# MCU.net
KiCad netlist of a schematic drawn in Altium Designer
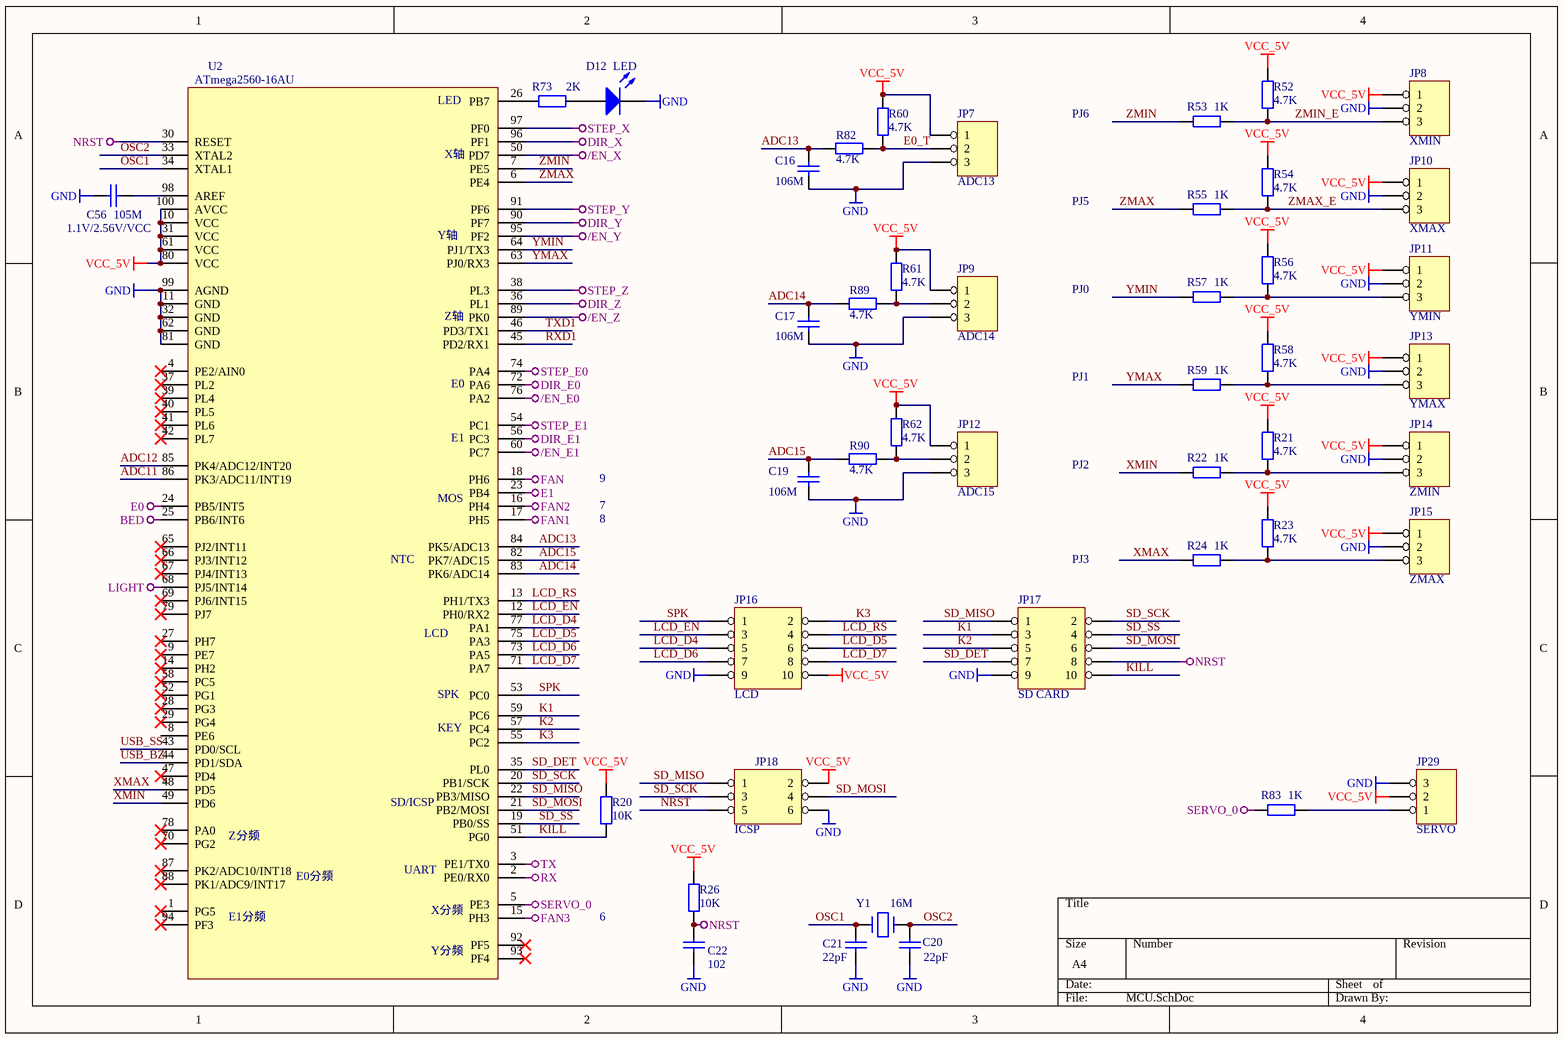
[diagram p0: MCU.SchDoc]

(export (version "E")
  (design (tool "Eeschema 10.0.6"))
  (components
    (comp (ref "C16")
      (value "106M")
      (footprint "0603(C)")
      (description "Capacitor")
      (fields (field (name "PUBLISHER") "Altium Limited"))
      (libsource (lib "Miscellaneous Devices") (part "Cap"))
    )
    (comp (ref "C17")
      (value "106M")
      (footprint "0603(C)")
      (description "Capacitor")
      (fields (field (name "PUBLISHER") "Altium Limited"))
      (libsource (lib "Miscellaneous Devices") (part "Cap"))
    )
    (comp (ref "C19")
      (value "106M")
      (footprint "0603(C)")
      (description "Capacitor")
      (fields (field (name "PUBLISHER") "Altium Limited"))
      (libsource (lib "Miscellaneous Devices") (part "Cap"))
    )
    (comp (ref "C20")
      (value "22pF")
      (footprint "0603(C)")
      (description "Capacitor")
      (fields (field (name "PUBLISHER") "Altium Limited"))
      (libsource (lib "Miscellaneous Devices") (part "Cap"))
    )
    (comp (ref "C21")
      (value "22pF")
      (footprint "0603(C)")
      (description "Capacitor")
      (fields (field (name "PUBLISHER") "Altium Limited"))
      (libsource (lib "Miscellaneous Devices") (part "Cap"))
    )
    (comp (ref "C22")
      (value "102")
      (footprint "0603(C)")
      (description "Capacitor")
      (fields (field (name "PUBLISHER") "Altium Limited"))
      (libsource (lib "Miscellaneous Devices") (part "Cap"))
    )
    (comp (ref "C56")
      (value "105M")
      (footprint "0603(C)")
      (description "Capacitor")
      (fields (field (name "PUBLISHER") "Altium Limited"))
      (libsource (lib "Miscellaneous Devices") (part "Cap"))
    )
    (comp (ref "D12")
      (value "LED")
      (footprint "LED-SMD-0805")
      (description "Typical RED GaAs LED")
      (fields (field (name "PUBLISHER") "Altium Limited"))
      (libsource (lib "Miscellaneous Devices") (part "LED1"))
    )
    (comp (ref "JP7") (value "ADC13") (footprint "XH2.54-3P") (libsource (lib "U_PP SCH") (part "HEADER 3")))
    (comp (ref "JP8") (value "XMIN") (footprint "XH2.54-3P") (libsource (lib "U_PP SCH") (part "HEADER 3")))
    (comp (ref "JP9") (value "ADC14") (footprint "XH2.54-3P") (libsource (lib "U_PP SCH") (part "HEADER 3")))
    (comp (ref "JP10") (value "XMAX") (footprint "XH2.54-3P") (libsource (lib "U_PP SCH") (part "HEADER 3")))
    (comp (ref "JP11") (value "YMIN") (footprint "XH2.54-3P") (libsource (lib "U_PP SCH") (part "HEADER 3")))
    (comp (ref "JP12") (value "ADC15") (footprint "XH2.54-3P") (libsource (lib "U_PP SCH") (part "HEADER 3")))
    (comp (ref "JP13") (value "YMAX") (footprint "XH2.54-3P") (libsource (lib "U_PP SCH") (part "HEADER 3")))
    (comp (ref "JP14") (value "ZMIN") (footprint "XH2.54-3P") (libsource (lib "U_PP SCH") (part "HEADER 3")))
    (comp (ref "JP15") (value "ZMAX") (footprint "XH2.54-3P") (libsource (lib "U_PP SCH") (part "HEADER 3")))
    (comp (ref "JP16")
      (value "LCD")
      (footprint "IDC10-BASE")
      (libsource (lib "U_PP SCH") (part "HEADER 5X2"))
    )
    (comp (ref "JP17")
      (value "SD CARD")
      (footprint "IDC10-BASE")
      (libsource (lib "U_PP SCH") (part "HEADER 5X2"))
    )
    (comp (ref "JP18")
      (value "ICSP")
      (footprint "IDC6X2.54")
      (libsource (lib "U_PP SCH") (part "HEADER 3X2"))
    )
    (comp (ref "JP29") (value "SERVO") (footprint "XH2.54-3P") (libsource (lib "") (part "HEADER 3_1")))
    (comp (ref "R20")
      (value "10K")
      (footprint "0603(R)")
      (description "1K")
      (fields (field (name "PUBLISHER") "Altium Limited"))
      (libsource (lib "") (part "Res2_2"))
    )
    (comp (ref "R21")
      (value "4.7K")
      (footprint "0603(R)")
      (description "1K")
      (fields (field (name "PUBLISHER") "Altium Limited"))
      (libsource (lib "") (part "Res2_1"))
    )
    (comp (ref "R22")
      (value "1K")
      (footprint "0603(R)")
      (fields (field (name "PUBLISHER") "Altium Limited"))
      (libsource (lib "Miscellaneous Devices") (part "Res2"))
    )
    (comp (ref "R23")
      (value "4.7K")
      (footprint "0603(R)")
      (description "1K")
      (fields (field (name "PUBLISHER") "Altium Limited"))
      (libsource (lib "") (part "Res2_1"))
    )
    (comp (ref "R24")
      (value "1K")
      (footprint "0603(R)")
      (fields (field (name "PUBLISHER") "Altium Limited"))
      (libsource (lib "Miscellaneous Devices") (part "Res2"))
    )
    (comp (ref "R26")
      (value "10K")
      (footprint "0603(R)")
      (description "1K")
      (fields (field (name "PUBLISHER") "Altium Limited"))
      (libsource (lib "") (part "Res2_2"))
    )
    (comp (ref "R52")
      (value "4.7K")
      (footprint "0603(R)")
      (description "1K")
      (fields (field (name "PUBLISHER") "Altium Limited"))
      (libsource (lib "") (part "Res2_1"))
    )
    (comp (ref "R53")
      (value "1K")
      (footprint "0603(R)")
      (fields (field (name "PUBLISHER") "Altium Limited"))
      (libsource (lib "Miscellaneous Devices") (part "Res2"))
    )
    (comp (ref "R54")
      (value "4.7K")
      (footprint "0603(R)")
      (description "1K")
      (fields (field (name "PUBLISHER") "Altium Limited"))
      (libsource (lib "") (part "Res2_1"))
    )
    (comp (ref "R55")
      (value "1K")
      (footprint "0603(R)")
      (fields (field (name "PUBLISHER") "Altium Limited"))
      (libsource (lib "Miscellaneous Devices") (part "Res2"))
    )
    (comp (ref "R56")
      (value "4.7K")
      (footprint "0603(R)")
      (description "1K")
      (fields (field (name "PUBLISHER") "Altium Limited"))
      (libsource (lib "") (part "Res2_1"))
    )
    (comp (ref "R57")
      (value "1K")
      (footprint "0603(R)")
      (fields (field (name "PUBLISHER") "Altium Limited"))
      (libsource (lib "Miscellaneous Devices") (part "Res2"))
    )
    (comp (ref "R58")
      (value "4.7K")
      (footprint "0603(R)")
      (description "1K")
      (fields (field (name "PUBLISHER") "Altium Limited"))
      (libsource (lib "") (part "Res2_1"))
    )
    (comp (ref "R59")
      (value "1K")
      (footprint "0603(R)")
      (fields (field (name "PUBLISHER") "Altium Limited"))
      (libsource (lib "Miscellaneous Devices") (part "Res2"))
    )
    (comp (ref "R60")
      (value "4.7K")
      (footprint "0603(R)")
      (description "1K")
      (fields (field (name "PUBLISHER") "Altium Limited"))
      (libsource (lib "") (part "Res2_1"))
    )
    (comp (ref "R61")
      (value "4.7K")
      (footprint "0603(R)")
      (description "1K")
      (fields (field (name "PUBLISHER") "Altium Limited"))
      (libsource (lib "") (part "Res2_1"))
    )
    (comp (ref "R62")
      (value "4.7K")
      (footprint "0603(R)")
      (description "1K")
      (fields (field (name "PUBLISHER") "Altium Limited"))
      (libsource (lib "") (part "Res2_1"))
    )
    (comp (ref "R73")
      (value "2K")
      (footprint "0603(R)")
      (description "Resistor")
      (libsource (lib "*") (part "Res2"))
    )
    (comp (ref "R82")
      (value "4.7K")
      (footprint "0603(R)")
      (description "1K")
      (fields (field (name "PUBLISHER") "Altium Limited"))
      (libsource (lib "") (part "Res2_3"))
    )
    (comp (ref "R83")
      (value "1K")
      (footprint "0603(R)")
      (fields (field (name "PUBLISHER") "Altium Limited"))
      (libsource (lib "Miscellaneous Devices") (part "Res2"))
    )
    (comp (ref "R89")
      (value "4.7K")
      (footprint "0603(R)")
      (description "1K")
      (fields (field (name "PUBLISHER") "Altium Limited"))
      (libsource (lib "") (part "Res2_3"))
    )
    (comp (ref "R90")
      (value "4.7K")
      (footprint "0603(R)")
      (description "1K")
      (fields (field (name "PUBLISHER") "Altium Limited"))
      (libsource (lib "") (part "Res2_3"))
    )
    (comp (ref "U2")
      (value "ATmega2560-16AU")
      (footprint "LQFP100")
      (libsource (lib "U_PP SCH") (part "ATmega2560"))
    )
    (comp (ref "Y1")
      (value "16M")
      (footprint "CRYS-SMD-5032-2P")
      (description "Crystal")
      (libsource (lib "Miscellaneous Devicespp1") (part "CRYSTAL"))
    )
  )
  (nets
    (net (code "1") (name "/ADC11") (class "Default")
      (node (ref "U2") (pin "86") (pinfunction "PK3/ADC11/INT19_86") (pintype "passive"))
    )
    (net (code "2") (name "/ADC12") (class "Default")
      (node (ref "U2") (pin "85") (pinfunction "PK4/ADC12/INT20_85") (pintype "passive"))
    )
    (net (code "3") (name "/ADC13") (class "Default")
      (node (ref "C16") (pin "2") (pinfunction "2_2") (pintype "passive"))
      (node (ref "R82") (pin "1") (pinfunction "1_1") (pintype "passive"))
      (node (ref "U2") (pin "84") (pinfunction "PK5/ADC13_84") (pintype "passive"))
    )
    (net (code "4") (name "/ADC14") (class "Default")
      (node (ref "C17") (pin "2") (pinfunction "2_2") (pintype "passive"))
      (node (ref "R89") (pin "1") (pinfunction "1_1") (pintype "passive"))
      (node (ref "U2") (pin "83") (pinfunction "PK6/ADC14_83") (pintype "passive"))
    )
    (net (code "5") (name "/ADC15") (class "Default")
      (node (ref "C19") (pin "2") (pinfunction "2_2") (pintype "passive"))
      (node (ref "R90") (pin "1") (pinfunction "1_1") (pintype "passive"))
      (node (ref "U2") (pin "82") (pinfunction "PK7/ADC15_82") (pintype "passive"))
    )
    (net (code "6") (name "/E0_T") (class "Default")
      (node (ref "JP7") (pin "2") (pinfunction "2_2") (pintype "passive"))
      (node (ref "R60") (pin "2") (pinfunction "2_2") (pintype "passive"))
      (node (ref "R82") (pin "2") (pinfunction "2_2") (pintype "passive"))
    )
    (net (code "7") (name "/K1") (class "Default")
      (node (ref "JP17") (pin "3") (pinfunction "3_3") (pintype "passive"))
      (node (ref "U2") (pin "59") (pinfunction "PC6_59") (pintype "passive"))
    )
    (net (code "8") (name "/K2") (class "Default")
      (node (ref "JP17") (pin "5") (pinfunction "5_5") (pintype "passive"))
      (node (ref "U2") (pin "57") (pinfunction "PC4_57") (pintype "passive"))
    )
    (net (code "9") (name "/K3") (class "Default")
      (node (ref "JP16") (pin "2") (pinfunction "2_2") (pintype "passive"))
      (node (ref "U2") (pin "55") (pinfunction "PC2_55") (pintype "passive"))
    )
    (net (code "10") (name "/KILL") (class "Default")
      (node (ref "JP17") (pin "10") (pinfunction "10_10") (pintype "passive"))
      (node (ref "R20") (pin "1") (pinfunction "1_1") (pintype "passive"))
      (node (ref "U2") (pin "51") (pinfunction "PG0_51") (pintype "passive"))
    )
    (net (code "11") (name "/LCD_D4") (class "Default")
      (node (ref "JP16") (pin "5") (pinfunction "5_5") (pintype "passive"))
      (node (ref "U2") (pin "77") (pinfunction "PA1_77") (pintype "passive"))
    )
    (net (code "12") (name "/LCD_D5") (class "Default")
      (node (ref "JP16") (pin "6") (pinfunction "6_6") (pintype "passive"))
      (node (ref "U2") (pin "75") (pinfunction "PA3_75") (pintype "passive"))
    )
    (net (code "13") (name "/LCD_D6") (class "Default")
      (node (ref "JP16") (pin "7") (pinfunction "7_7") (pintype "passive"))
      (node (ref "U2") (pin "73") (pinfunction "PA5_73") (pintype "passive"))
    )
    (net (code "14") (name "/LCD_D7") (class "Default")
      (node (ref "JP16") (pin "8") (pinfunction "8_8") (pintype "passive"))
      (node (ref "U2") (pin "71") (pinfunction "PA7_71") (pintype "passive"))
    )
    (net (code "15") (name "/LCD_EN") (class "Default")
      (node (ref "JP16") (pin "3") (pinfunction "3_3") (pintype "passive"))
      (node (ref "U2") (pin "12") (pinfunction "PH0/RX2_12") (pintype "passive"))
    )
    (net (code "16") (name "/LCD_RS") (class "Default")
      (node (ref "JP16") (pin "4") (pinfunction "4_4") (pintype "passive"))
      (node (ref "U2") (pin "13") (pinfunction "PH1/TX3_13") (pintype "passive"))
    )
    (net (code "17") (name "/OSC1") (class "Default")
      (node (ref "C21") (pin "1") (pinfunction "1_1") (pintype "passive"))
      (node (ref "U2") (pin "34") (pinfunction "XTAL1_34") (pintype "passive"))
      (node (ref "Y1") (pin "1") (pinfunction "1_1") (pintype "passive"))
    )
    (net (code "18") (name "/OSC2") (class "Default")
      (node (ref "C20") (pin "1") (pinfunction "1_1") (pintype "passive"))
      (node (ref "U2") (pin "33") (pinfunction "XTAL2_33") (pintype "passive"))
      (node (ref "Y1") (pin "2") (pinfunction "2_2") (pintype "passive"))
    )
    (net (code "19") (name "/RXD1") (class "Default")
      (node (ref "U2") (pin "45") (pinfunction "PD2/RX1_45") (pintype "passive"))
    )
    (net (code "20") (name "/SD_DET") (class "Default")
      (node (ref "JP17") (pin "7") (pinfunction "7_7") (pintype "passive"))
      (node (ref "U2") (pin "35") (pinfunction "PL0_35") (pintype "passive"))
    )
    (net (code "21") (name "/SD_MISO") (class "Default")
      (node (ref "JP17") (pin "1") (pinfunction "1_1") (pintype "passive"))
      (node (ref "JP18") (pin "1") (pinfunction "1_1") (pintype "passive"))
      (node (ref "U2") (pin "22") (pinfunction "PB3/MISO_22") (pintype "passive"))
    )
    (net (code "22") (name "/SD_MOSI") (class "Default")
      (node (ref "JP17") (pin "6") (pinfunction "6_6") (pintype "passive"))
      (node (ref "JP18") (pin "4") (pinfunction "4_4") (pintype "passive"))
      (node (ref "U2") (pin "21") (pinfunction "PB2/MOSI_21") (pintype "passive"))
    )
    (net (code "23") (name "/SD_SCK") (class "Default")
      (node (ref "JP17") (pin "2") (pinfunction "2_2") (pintype "passive"))
      (node (ref "JP18") (pin "3") (pinfunction "3_3") (pintype "passive"))
      (node (ref "U2") (pin "20") (pinfunction "PB1/SCK_20") (pintype "passive"))
    )
    (net (code "24") (name "/SD_SS") (class "Default")
      (node (ref "JP17") (pin "4") (pinfunction "4_4") (pintype "passive"))
      (node (ref "U2") (pin "19") (pinfunction "PB0/SS_19") (pintype "passive"))
    )
    (net (code "25") (name "/SPK") (class "Default")
      (node (ref "JP16") (pin "1") (pinfunction "1_1") (pintype "passive"))
      (node (ref "U2") (pin "53") (pinfunction "PC0_53") (pintype "passive"))
    )
    (net (code "26") (name "/TXD1") (class "Default")
      (node (ref "U2") (pin "46") (pinfunction "PD3/TX1_46") (pintype "passive"))
    )
    (net (code "27") (name "/USB_BZ") (class "Default")
      (node (ref "U2") (pin "44") (pinfunction "PD1/SDA_44") (pintype "passive"))
    )
    (net (code "28") (name "/USB_SS") (class "Default")
      (node (ref "U2") (pin "43") (pinfunction "PD0/SCL_43") (pintype "passive"))
    )
    (net (code "29") (name "/XMAX") (class "Default")
      (node (ref "R24") (pin "2") (pinfunction "2_2") (pintype "passive"))
      (node (ref "U2") (pin "48") (pinfunction "PD5_48") (pintype "passive"))
    )
    (net (code "30") (name "/XMIN") (class "Default")
      (node (ref "R22") (pin "2") (pinfunction "2_2") (pintype "passive"))
      (node (ref "U2") (pin "49") (pinfunction "PD6_49") (pintype "passive"))
    )
    (net (code "31") (name "/YMAX") (class "Default")
      (node (ref "R59") (pin "2") (pinfunction "2_2") (pintype "passive"))
      (node (ref "U2") (pin "63") (pinfunction "PJ0/RX3_63") (pintype "passive"))
    )
    (net (code "32") (name "/YMIN") (class "Default")
      (node (ref "R57") (pin "2") (pinfunction "2_2") (pintype "passive"))
      (node (ref "U2") (pin "64") (pinfunction "PJ1/TX3_64") (pintype "passive"))
    )
    (net (code "33") (name "/ZMAX") (class "Default")
      (node (ref "R55") (pin "2") (pinfunction "2_2") (pintype "passive"))
      (node (ref "U2") (pin "6") (pinfunction "PE4_6") (pintype "passive"))
    )
    (net (code "34") (name "/ZMAX_E") (class "Default")
      (node (ref "JP10") (pin "3") (pinfunction "3_3") (pintype "passive"))
      (node (ref "R54") (pin "2") (pinfunction "2_2") (pintype "passive"))
      (node (ref "R55") (pin "1") (pinfunction "1_1") (pintype "passive"))
    )
    (net (code "35") (name "/ZMIN") (class "Default")
      (node (ref "R53") (pin "2") (pinfunction "2_2") (pintype "passive"))
      (node (ref "U2") (pin "7") (pinfunction "PE5_7") (pintype "passive"))
    )
    (net (code "36") (name "/ZMIN_E") (class "Default")
      (node (ref "JP8") (pin "3") (pinfunction "3_3") (pintype "passive"))
      (node (ref "R52") (pin "2") (pinfunction "2_2") (pintype "passive"))
      (node (ref "R53") (pin "1") (pinfunction "1_1") (pintype "passive"))
    )
    (net (code "37") (name "BED") (class "Default")
      (node (ref "U2") (pin "25") (pinfunction "PB6/INT6_25") (pintype "passive"))
    )
    (net (code "38") (name "DIR_E0") (class "Default")
      (node (ref "U2") (pin "72") (pinfunction "PA6_72") (pintype "passive"))
    )
    (net (code "39") (name "DIR_E1") (class "Default")
      (node (ref "U2") (pin "56") (pinfunction "PC3_56") (pintype "passive"))
    )
    (net (code "40") (name "DIR_X") (class "Default")
      (node (ref "U2") (pin "96") (pinfunction "PF1_96") (pintype "passive"))
    )
    (net (code "41") (name "DIR_Y") (class "Default")
      (node (ref "U2") (pin "90") (pinfunction "PF7_90") (pintype "passive"))
    )
    (net (code "42") (name "DIR_Z") (class "Default")
      (node (ref "U2") (pin "36") (pinfunction "PL1_36") (pintype "passive"))
    )
    (net (code "43") (name "E0") (class "Default")
      (node (ref "U2") (pin "24") (pinfunction "PB5/INT5_24") (pintype "passive"))
    )
    (net (code "44") (name "E1") (class "Default")
      (node (ref "U2") (pin "23") (pinfunction "PB4_23") (pintype "passive"))
    )
    (net (code "45") (name "FAN") (class "Default")
      (node (ref "U2") (pin "18") (pinfunction "PH6_18") (pintype "passive"))
    )
    (net (code "46") (name "FAN1") (class "Default")
      (node (ref "U2") (pin "17") (pinfunction "PH5_17") (pintype "passive"))
    )
    (net (code "47") (name "FAN2") (class "Default")
      (node (ref "U2") (pin "16") (pinfunction "PH4_16") (pintype "passive"))
    )
    (net (code "48") (name "FAN3") (class "Default")
      (node (ref "U2") (pin "15") (pinfunction "PH3_15") (pintype "passive"))
    )
    (net (code "49") (name "GND") (class "Default")
      (node (ref "C16") (pin "1") (pinfunction "1_1") (pintype "passive"))
      (node (ref "C17") (pin "1") (pinfunction "1_1") (pintype "passive"))
      (node (ref "C19") (pin "1") (pinfunction "1_1") (pintype "passive"))
      (node (ref "C20") (pin "2") (pinfunction "2_2") (pintype "passive"))
      (node (ref "C21") (pin "2") (pinfunction "2_2") (pintype "passive"))
      (node (ref "C22") (pin "2") (pinfunction "2_2") (pintype "passive"))
      (node (ref "C56") (pin "2") (pinfunction "2_2") (pintype "passive"))
      (node (ref "D12") (pin "2") (pinfunction "K_2") (pintype "passive"))
      (node (ref "JP10") (pin "2") (pinfunction "2_2") (pintype "passive"))
      (node (ref "JP11") (pin "2") (pinfunction "2_2") (pintype "passive"))
      (node (ref "JP12") (pin "3") (pinfunction "3_3") (pintype "passive"))
      (node (ref "JP13") (pin "2") (pinfunction "2_2") (pintype "passive"))
      (node (ref "JP14") (pin "2") (pinfunction "2_2") (pintype "passive"))
      (node (ref "JP15") (pin "2") (pinfunction "2_2") (pintype "passive"))
      (node (ref "JP16") (pin "9") (pinfunction "9_9") (pintype "passive"))
      (node (ref "JP17") (pin "9") (pinfunction "9_9") (pintype "passive"))
      (node (ref "JP18") (pin "6") (pinfunction "6_6") (pintype "passive"))
      (node (ref "JP29") (pin "3") (pinfunction "3_3") (pintype "passive"))
      (node (ref "JP7") (pin "3") (pinfunction "3_3") (pintype "passive"))
      (node (ref "JP8") (pin "2") (pinfunction "2_2") (pintype "passive"))
      (node (ref "JP9") (pin "3") (pinfunction "3_3") (pintype "passive"))
      (node (ref "U2") (pin "11") (pinfunction "GND_11") (pintype "passive"))
      (node (ref "U2") (pin "32") (pinfunction "GND_32") (pintype "passive"))
      (node (ref "U2") (pin "62") (pinfunction "GND_62") (pintype "passive"))
      (node (ref "U2") (pin "81") (pinfunction "GND_81") (pintype "passive"))
      (node (ref "U2") (pin "99") (pinfunction "AGND_99") (pintype "passive"))
    )
    (net (code "50") (name "LIGHT") (class "Default")
      (node (ref "U2") (pin "68") (pinfunction "PJ5/INT14_68") (pintype "passive"))
    )
    (net (code "51") (name "NRST") (class "Default")
      (node (ref "C22") (pin "1") (pinfunction "1_1") (pintype "passive"))
      (node (ref "JP17") (pin "8") (pinfunction "8_8") (pintype "passive"))
      (node (ref "JP18") (pin "5") (pinfunction "5_5") (pintype "passive"))
      (node (ref "R26") (pin "1") (pinfunction "1_1") (pintype "passive"))
      (node (ref "U2") (pin "30") (pinfunction "RESET_30") (pintype "passive"))
    )
    (net (code "52") (name "Net-(D12-A)") (class "Default")
      (node (ref "D12") (pin "1") (pinfunction "A_1") (pintype "passive"))
      (node (ref "R73") (pin "2") (pinfunction "2_2") (pintype "passive"))
    )
    (net (code "53") (name "Net-(JP9-Pad2)") (class "Default")
      (node (ref "JP9") (pin "2") (pinfunction "2_2") (pintype "passive"))
      (node (ref "R61") (pin "2") (pinfunction "2_2") (pintype "passive"))
      (node (ref "R89") (pin "2") (pinfunction "2_2") (pintype "passive"))
    )
    (net (code "54") (name "Net-(JP11-Pad3)") (class "Default")
      (node (ref "JP11") (pin "3") (pinfunction "3_3") (pintype "passive"))
      (node (ref "R56") (pin "2") (pinfunction "2_2") (pintype "passive"))
      (node (ref "R57") (pin "1") (pinfunction "1_1") (pintype "passive"))
    )
    (net (code "55") (name "Net-(JP12-Pad2)") (class "Default")
      (node (ref "JP12") (pin "2") (pinfunction "2_2") (pintype "passive"))
      (node (ref "R62") (pin "2") (pinfunction "2_2") (pintype "passive"))
      (node (ref "R90") (pin "2") (pinfunction "2_2") (pintype "passive"))
    )
    (net (code "56") (name "Net-(JP13-Pad3)") (class "Default")
      (node (ref "JP13") (pin "3") (pinfunction "3_3") (pintype "passive"))
      (node (ref "R58") (pin "2") (pinfunction "2_2") (pintype "passive"))
      (node (ref "R59") (pin "1") (pinfunction "1_1") (pintype "passive"))
    )
    (net (code "57") (name "Net-(JP14-Pad3)") (class "Default")
      (node (ref "JP14") (pin "3") (pinfunction "3_3") (pintype "passive"))
      (node (ref "R21") (pin "2") (pinfunction "2_2") (pintype "passive"))
      (node (ref "R22") (pin "1") (pinfunction "1_1") (pintype "passive"))
    )
    (net (code "58") (name "Net-(JP15-Pad3)") (class "Default")
      (node (ref "JP15") (pin "3") (pinfunction "3_3") (pintype "passive"))
      (node (ref "R23") (pin "2") (pinfunction "2_2") (pintype "passive"))
      (node (ref "R24") (pin "1") (pinfunction "1_1") (pintype "passive"))
    )
    (net (code "59") (name "Net-(JP29-Pad1)") (class "Default")
      (node (ref "JP29") (pin "1") (pinfunction "1_1") (pintype "passive"))
      (node (ref "R83") (pin "1") (pinfunction "1_1") (pintype "passive"))
    )
    (net (code "60") (name "Net-(U2-AREF)") (class "Default")
      (node (ref "C56") (pin "1") (pinfunction "1_1") (pintype "passive"))
      (node (ref "U2") (pin "98") (pinfunction "AREF_98") (pintype "passive"))
    )
    (net (code "61") (name "Net-(U2-PB7)") (class "Default")
      (node (ref "R73") (pin "1") (pinfunction "1_1") (pintype "passive"))
      (node (ref "U2") (pin "26") (pinfunction "PB7_26") (pintype "passive"))
    )
    (net (code "62") (name "RX") (class "Default")
      (node (ref "U2") (pin "2") (pinfunction "PE0/RX0_2") (pintype "passive"))
    )
    (net (code "63") (name "SERVO_0") (class "Default")
      (node (ref "R83") (pin "2") (pinfunction "2_2") (pintype "passive"))
      (node (ref "U2") (pin "5") (pinfunction "PE3_5") (pintype "passive"))
    )
    (net (code "64") (name "STEP_E0") (class "Default")
      (node (ref "U2") (pin "74") (pinfunction "PA4_74") (pintype "passive"))
    )
    (net (code "65") (name "STEP_E1") (class "Default")
      (node (ref "U2") (pin "54") (pinfunction "PC1_54") (pintype "passive"))
    )
    (net (code "66") (name "STEP_X") (class "Default")
      (node (ref "U2") (pin "97") (pinfunction "PF0_97") (pintype "passive"))
    )
    (net (code "67") (name "STEP_Y") (class "Default")
      (node (ref "U2") (pin "91") (pinfunction "PF6_91") (pintype "passive"))
    )
    (net (code "68") (name "STEP_Z") (class "Default")
      (node (ref "U2") (pin "38") (pinfunction "PL3_38") (pintype "passive"))
    )
    (net (code "69") (name "TX") (class "Default")
      (node (ref "U2") (pin "3") (pinfunction "PE1/TX0_3") (pintype "passive"))
    )
    (net (code "70") (name "VCC_5V") (class "Default")
      (node (ref "JP10") (pin "1") (pinfunction "1_1") (pintype "passive"))
      (node (ref "JP11") (pin "1") (pinfunction "1_1") (pintype "passive"))
      (node (ref "JP12") (pin "1") (pinfunction "1_1") (pintype "passive"))
      (node (ref "JP13") (pin "1") (pinfunction "1_1") (pintype "passive"))
      (node (ref "JP14") (pin "1") (pinfunction "1_1") (pintype "passive"))
      (node (ref "JP15") (pin "1") (pinfunction "1_1") (pintype "passive"))
      (node (ref "JP16") (pin "10") (pinfunction "10_10") (pintype "passive"))
      (node (ref "JP18") (pin "2") (pinfunction "2_2") (pintype "passive"))
      (node (ref "JP29") (pin "2") (pinfunction "2_2") (pintype "passive"))
      (node (ref "JP7") (pin "1") (pinfunction "1_1") (pintype "passive"))
      (node (ref "JP8") (pin "1") (pinfunction "1_1") (pintype "passive"))
      (node (ref "JP9") (pin "1") (pinfunction "1_1") (pintype "passive"))
      (node (ref "R20") (pin "2") (pinfunction "2_2") (pintype "passive"))
      (node (ref "R21") (pin "1") (pinfunction "1_1") (pintype "passive"))
      (node (ref "R23") (pin "1") (pinfunction "1_1") (pintype "passive"))
      (node (ref "R26") (pin "2") (pinfunction "2_2") (pintype "passive"))
      (node (ref "R52") (pin "1") (pinfunction "1_1") (pintype "passive"))
      (node (ref "R54") (pin "1") (pinfunction "1_1") (pintype "passive"))
      (node (ref "R56") (pin "1") (pinfunction "1_1") (pintype "passive"))
      (node (ref "R58") (pin "1") (pinfunction "1_1") (pintype "passive"))
      (node (ref "R60") (pin "1") (pinfunction "1_1") (pintype "passive"))
      (node (ref "R61") (pin "1") (pinfunction "1_1") (pintype "passive"))
      (node (ref "R62") (pin "1") (pinfunction "1_1") (pintype "passive"))
      (node (ref "U2") (pin "10") (pinfunction "VCC_10") (pintype "passive"))
      (node (ref "U2") (pin "100") (pinfunction "AVCC_100") (pintype "passive"))
      (node (ref "U2") (pin "31") (pinfunction "VCC_31") (pintype "passive"))
      (node (ref "U2") (pin "61") (pinfunction "VCC_61") (pintype "passive"))
      (node (ref "U2") (pin "80") (pinfunction "VCC_80") (pintype "passive"))
    )
    (net (code "71") (name "unconnected-(U2-PA0-Pad78)") (class "Default")
      (node (ref "U2") (pin "78") (pinfunction "PA0_78") (pintype "passive+no_connect"))
    )
    (net (code "72") (name "unconnected-(U2-PC5-Pad58)") (class "Default")
      (node (ref "U2") (pin "58") (pinfunction "PC5_58") (pintype "passive+no_connect"))
    )
    (net (code "73") (name "unconnected-(U2-PD4-Pad47)") (class "Default")
      (node (ref "U2") (pin "47") (pinfunction "PD4_47") (pintype "passive+no_connect"))
    )
    (net (code "74") (name "unconnected-(U2-PE2{slash}AIN0-Pad4)") (class "Default")
      (node (ref "U2") (pin "4") (pinfunction "PE2/AIN0_4") (pintype "passive+no_connect"))
    )
    (net (code "75") (name "unconnected-(U2-PE6-Pad8)") (class "Default")
      (node (ref "U2") (pin "8") (pinfunction "PE6_8") (pintype "passive"))
    )
    (net (code "76") (name "unconnected-(U2-PE7-Pad9)") (class "Default")
      (node (ref "U2") (pin "9") (pinfunction "PE7_9") (pintype "passive+no_connect"))
    )
    (net (code "77") (name "unconnected-(U2-PF3-Pad94)") (class "Default")
      (node (ref "U2") (pin "94") (pinfunction "PF3_94") (pintype "passive+no_connect"))
    )
    (net (code "78") (name "unconnected-(U2-PF4-Pad93)") (class "Default")
      (node (ref "U2") (pin "93") (pinfunction "PF4_93") (pintype "passive+no_connect"))
    )
    (net (code "79") (name "unconnected-(U2-PF5-Pad92)") (class "Default")
      (node (ref "U2") (pin "92") (pinfunction "PF5_92") (pintype "passive+no_connect"))
    )
    (net (code "80") (name "unconnected-(U2-PG1-Pad52)") (class "Default")
      (node (ref "U2") (pin "52") (pinfunction "PG1_52") (pintype "passive+no_connect"))
    )
    (net (code "81") (name "unconnected-(U2-PG2-Pad70)") (class "Default")
      (node (ref "U2") (pin "70") (pinfunction "PG2_70") (pintype "passive+no_connect"))
    )
    (net (code "82") (name "unconnected-(U2-PG3-Pad28)") (class "Default")
      (node (ref "U2") (pin "28") (pinfunction "PG3_28") (pintype "passive+no_connect"))
    )
    (net (code "83") (name "unconnected-(U2-PG4-Pad29)") (class "Default")
      (node (ref "U2") (pin "29") (pinfunction "PG4_29") (pintype "passive+no_connect"))
    )
    (net (code "84") (name "unconnected-(U2-PG5-Pad1)") (class "Default")
      (node (ref "U2") (pin "1") (pinfunction "PG5_1") (pintype "passive+no_connect"))
    )
    (net (code "85") (name "unconnected-(U2-PH2-Pad14)") (class "Default")
      (node (ref "U2") (pin "14") (pinfunction "PH2_14") (pintype "passive+no_connect"))
    )
    (net (code "86") (name "unconnected-(U2-PH7-Pad27)") (class "Default")
      (node (ref "U2") (pin "27") (pinfunction "PH7_27") (pintype "passive+no_connect"))
    )
    (net (code "87") (name "unconnected-(U2-PJ2{slash}INT11-Pad65)") (class "Default")
      (node (ref "U2") (pin "65") (pinfunction "PJ2/INT11_65") (pintype "passive+no_connect"))
    )
    (net (code "88") (name "unconnected-(U2-PJ3{slash}INT12-Pad66)") (class "Default")
      (node (ref "U2") (pin "66") (pinfunction "PJ3/INT12_66") (pintype "passive+no_connect"))
    )
    (net (code "89") (name "unconnected-(U2-PJ4{slash}INT13-Pad67)") (class "Default")
      (node (ref "U2") (pin "67") (pinfunction "PJ4/INT13_67") (pintype "passive+no_connect"))
    )
    (net (code "90") (name "unconnected-(U2-PJ6{slash}INT15-Pad69)") (class "Default")
      (node (ref "U2") (pin "69") (pinfunction "PJ6/INT15_69") (pintype "passive+no_connect"))
    )
    (net (code "91") (name "unconnected-(U2-PJ7-Pad79)") (class "Default")
      (node (ref "U2") (pin "79") (pinfunction "PJ7_79") (pintype "passive+no_connect"))
    )
    (net (code "92") (name "unconnected-(U2-PK1{slash}ADC9{slash}INT17-Pad88)") (class "Default")
      (node (ref "U2") (pin "88") (pinfunction "PK1/ADC9/INT17_88") (pintype "passive+no_connect"))
    )
    (net (code "93") (name "unconnected-(U2-PK2{slash}ADC10{slash}INT18-Pad87)") (class "Default")
      (node (ref "U2") (pin "87") (pinfunction "PK2/ADC10/INT18_87") (pintype "passive+no_connect"))
    )
    (net (code "94") (name "unconnected-(U2-PL2-Pad37)") (class "Default")
      (node (ref "U2") (pin "37") (pinfunction "PL2_37") (pintype "passive+no_connect"))
    )
    (net (code "95") (name "unconnected-(U2-PL4-Pad39)") (class "Default")
      (node (ref "U2") (pin "39") (pinfunction "PL4_39") (pintype "passive+no_connect"))
    )
    (net (code "96") (name "unconnected-(U2-PL5-Pad40)") (class "Default")
      (node (ref "U2") (pin "40") (pinfunction "PL5_40") (pintype "passive+no_connect"))
    )
    (net (code "97") (name "unconnected-(U2-PL6-Pad41)") (class "Default")
      (node (ref "U2") (pin "41") (pinfunction "PL6_41") (pintype "passive+no_connect"))
    )
    (net (code "98") (name "unconnected-(U2-PL7-Pad42)") (class "Default")
      (node (ref "U2") (pin "42") (pinfunction "PL7_42") (pintype "passive+no_connect"))
    )
    (net (code "99") (name "{slash}EN_E0") (class "Default")
      (node (ref "U2") (pin "76") (pinfunction "PA2_76") (pintype "passive"))
    )
    (net (code "100") (name "{slash}EN_E1") (class "Default")
      (node (ref "U2") (pin "60") (pinfunction "PC7_60") (pintype "passive"))
    )
    (net (code "101") (name "{slash}EN_X") (class "Default")
      (node (ref "U2") (pin "50") (pinfunction "PD7_50") (pintype "passive"))
    )
    (net (code "102") (name "{slash}EN_Y") (class "Default")
      (node (ref "U2") (pin "95") (pinfunction "PF2_95") (pintype "passive"))
    )
    (net (code "103") (name "{slash}EN_Z") (class "Default")
      (node (ref "U2") (pin "89") (pinfunction "PK0_89") (pintype "passive"))
    )
  )
)
